# lin_reg_schematic_forpcb.net
KiCad netlist of a schematic drawn in EAGLE
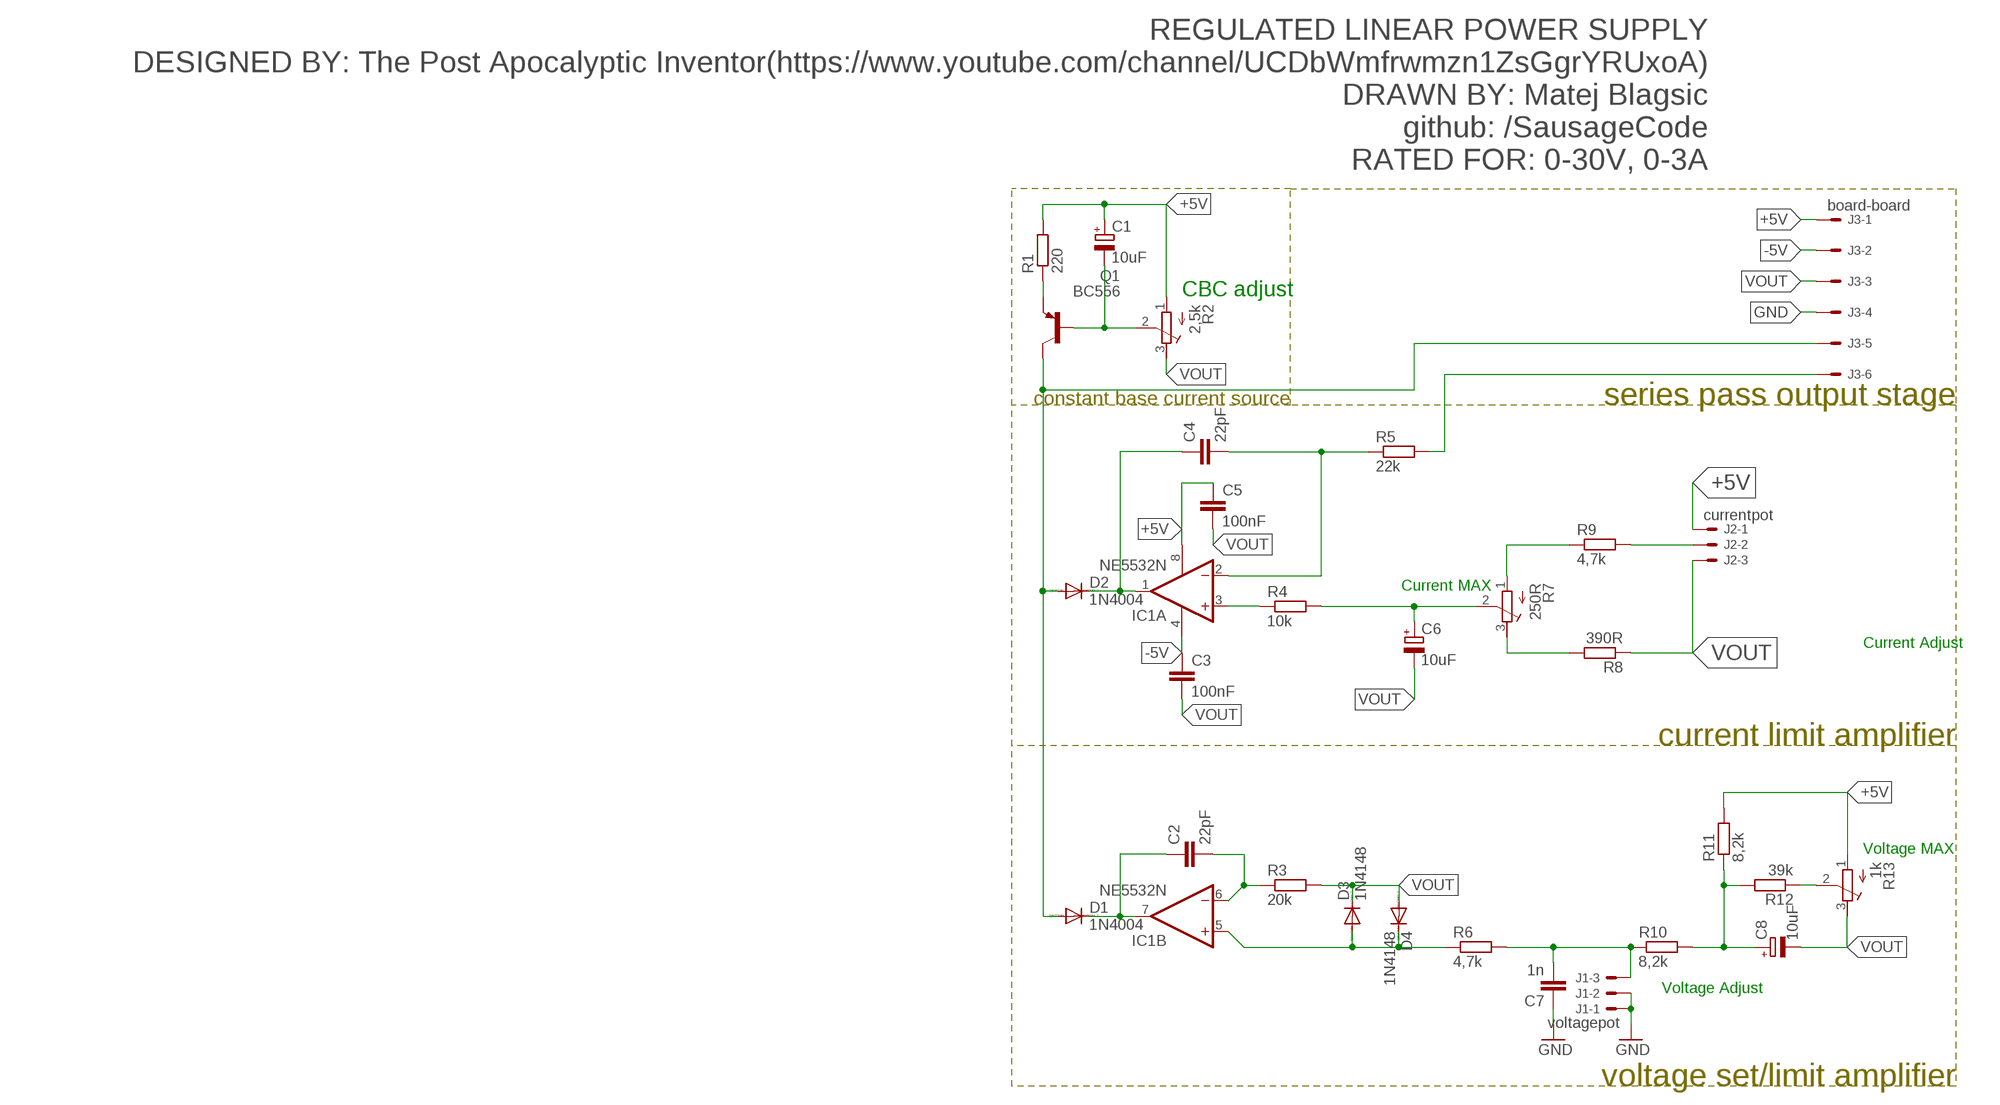
[diagram p0: schematic, sheet 1]

(export (version "E")
  (design (tool "Eeschema 10.0.6"))
  (components
    (comp (ref "C1")
      (value "10uF")
      (footprint "eagle-import:E2,5-5")
      (libsource (lib "eagle-import") (part "CPOL-EUE2.5-5"))
    )
    (comp (ref "C2")
      (value "22pF")
      (footprint "eagle-import:C025-025X050")
      (libsource (lib "eagle-import") (part "C-EU025-025X050"))
    )
    (comp (ref "C3")
      (value "100nF")
      (footprint "eagle-import:C025-025X050")
      (libsource (lib "eagle-import") (part "C-EU025-025X050"))
    )
    (comp (ref "C4")
      (value "22pF")
      (footprint "eagle-import:C025-025X050")
      (libsource (lib "eagle-import") (part "C-EU025-025X050"))
    )
    (comp (ref "C5")
      (value "100nF")
      (footprint "eagle-import:C025-025X050")
      (libsource (lib "eagle-import") (part "C-EU025-025X050"))
    )
    (comp (ref "C6")
      (value "10uF")
      (footprint "eagle-import:E2,5-5")
      (libsource (lib "eagle-import") (part "CPOL-EUE2.5-5"))
    )
    (comp (ref "C7")
      (value "1n")
      (footprint "eagle-import:C025-025X050")
      (libsource (lib "eagle-import") (part "C-EU025-025X050"))
    )
    (comp (ref "C8")
      (value "10uF")
      (footprint "eagle-import:E2,5-5")
      (libsource (lib "eagle-import") (part "CPOL-EUE2.5-5"))
    )
    (comp (ref "D1")
      (value "1N4004")
      (footprint "eagle-import:DO41-10")
      (libsource (lib "eagle-import") (part "1N4004"))
    )
    (comp (ref "D2")
      (value "1N4004")
      (footprint "eagle-import:DO41-10")
      (libsource (lib "eagle-import") (part "1N4004"))
    )
    (comp (ref "D3")
      (value "1N4148")
      (footprint "eagle-import:DO41-10")
      (libsource (lib "eagle-import") (part "1N4004"))
    )
    (comp (ref "D4")
      (value "1N4148")
      (footprint "eagle-import:DO41-10")
      (libsource (lib "eagle-import") (part "1N4004"))
    )
    (comp (ref "IC1")
      (value "NE5532N")
      (footprint "eagle-import:DIL08")
      (libsource (lib "eagle-import") (part "NE5532N"))
    )
    (comp (ref "J1")
      (value "voltagepot")
      (footprint "eagle-import:6410-03")
      (libsource (lib "eagle-import") (part "22-?-0327-2031"))
    )
    (comp (ref "J2")
      (value "currentpot")
      (footprint "eagle-import:6410-03")
      (libsource (lib "eagle-import") (part "22-?-0327-2031"))
    )
    (comp (ref "J3")
      (value "board-board")
      (footprint "eagle-import:6410-06")
      (libsource (lib "eagle-import") (part "22-?-0627-2061"))
    )
    (comp (ref "Q1")
      (value "BC556")
      (footprint "eagle-import:TO92-EBC")
      (libsource (lib "eagle-import") (part "BC556"))
    )
    (comp (ref "R1")
      (value "220")
      (footprint "eagle-import:0207_10")
      (libsource (lib "eagle-import") (part "R-EU_0207/10"))
    )
    (comp (ref "R2")
      (value "2,5k")
      (footprint "eagle-import:RTRIM64W")
      (libsource (lib "eagle-import") (part "R-TRIMM64W"))
    )
    (comp (ref "R3")
      (value "20k")
      (footprint "eagle-import:0207_10")
      (libsource (lib "eagle-import") (part "R-EU_0207/10"))
    )
    (comp (ref "R4")
      (value "10k")
      (footprint "eagle-import:0207_10")
      (libsource (lib "eagle-import") (part "R-EU_0207/10"))
    )
    (comp (ref "R5")
      (value "22k")
      (footprint "eagle-import:0207_10")
      (libsource (lib "eagle-import") (part "R-EU_0207/10"))
    )
    (comp (ref "R6")
      (value "4,7k")
      (footprint "eagle-import:0207_10")
      (libsource (lib "eagle-import") (part "R-EU_0207/10"))
    )
    (comp (ref "R7")
      (value "250R")
      (footprint "eagle-import:RTRIM64W")
      (libsource (lib "eagle-import") (part "R-TRIMM64W"))
    )
    (comp (ref "R8")
      (value "390R")
      (footprint "eagle-import:0207_10")
      (libsource (lib "eagle-import") (part "resistor_348_R-EU_0207/10"))
    )
    (comp (ref "R9")
      (value "4,7k")
      (footprint "eagle-import:0207_10")
      (libsource (lib "eagle-import") (part "resistor_348_R-EU_0207/10"))
    )
    (comp (ref "R10")
      (value "8,2k")
      (footprint "eagle-import:0207_10")
      (libsource (lib "eagle-import") (part "R-EU_0207/10"))
    )
    (comp (ref "R11")
      (value "8,2k")
      (footprint "eagle-import:0207_10")
      (libsource (lib "eagle-import") (part "R-EU_0207/10"))
    )
    (comp (ref "R12")
      (value "39k")
      (footprint "eagle-import:0207_10")
      (libsource (lib "eagle-import") (part "R-EU_0207/10"))
    )
    (comp (ref "R13")
      (value "1k")
      (footprint "eagle-import:RTRIM64W")
      (libsource (lib "eagle-import") (part "R-TRIMM64W"))
    )
  )
  (nets
    (net (code "1") (name "+5V") (class "Default")
      (node (ref "C1") (pin "+") (pinfunction "+_+") (pintype "passive"))
      (node (ref "C5") (pin "1") (pinfunction "1_1") (pintype "passive"))
      (node (ref "IC1") (pin "8") (pinfunction "V+_8") (pintype "power_in"))
      (node (ref "J2") (pin "1") (pinfunction "S_1") (pintype "passive"))
      (node (ref "J3") (pin "1") (pinfunction "S_1") (pintype "passive"))
      (node (ref "R1") (pin "2") (pinfunction "2_2") (pintype "passive"))
      (node (ref "R11") (pin "2") (pinfunction "2_2") (pintype "passive"))
      (node (ref "R13") (pin "1") (pinfunction "A_1") (pintype "passive"))
      (node (ref "R2") (pin "1") (pinfunction "A_1") (pintype "passive"))
    )
    (net (code "2") (name "-5V") (class "Default")
      (node (ref "C3") (pin "1") (pinfunction "1_1") (pintype "passive"))
      (node (ref "IC1") (pin "4") (pinfunction "V-_4") (pintype "power_in"))
      (node (ref "J3") (pin "2") (pinfunction "S_2") (pintype "passive"))
    )
    (net (code "3") (name "GND") (class "Default")
      (node (ref "C7") (pin "1") (pinfunction "1_1") (pintype "passive"))
      (node (ref "J1") (pin "1") (pinfunction "S_1") (pintype "passive"))
      (node (ref "J1") (pin "2") (pinfunction "S_2") (pintype "passive"))
      (node (ref "J3") (pin "4") (pinfunction "S_4") (pintype "passive"))
    )
    (net (code "4") (name "Net-(C8-Pad+)") (class "Default")
      (node (ref "C8") (pin "+") (pinfunction "+_+") (pintype "passive"))
      (node (ref "R10") (pin "2") (pinfunction "2_2") (pintype "passive"))
      (node (ref "R11") (pin "1") (pinfunction "1_1") (pintype "passive"))
      (node (ref "R12") (pin "2") (pinfunction "2_2") (pintype "passive"))
    )
    (net (code "5") (name "Net-(IC1A-+IN)") (class "Default")
      (node (ref "IC1") (pin "3") (pinfunction "+IN_3") (pintype "input"))
      (node (ref "R4") (pin "1") (pinfunction "1_1") (pintype "passive"))
    )
    (net (code "6") (name "Net-(IC1A--IN)") (class "Default")
      (node (ref "C4") (pin "2") (pinfunction "2_2") (pintype "passive"))
      (node (ref "IC1") (pin "2") (pinfunction "-IN_2") (pintype "input"))
      (node (ref "R5") (pin "1") (pinfunction "1_1") (pintype "passive"))
    )
    (net (code "7") (name "Net-(IC1A-OUT)") (class "Default")
      (node (ref "C4") (pin "1") (pinfunction "1_1") (pintype "passive"))
      (node (ref "D2") (pin "C") (pinfunction "C_C") (pintype "passive"))
      (node (ref "IC1") (pin "1") (pinfunction "OUT_1") (pintype "output"))
    )
    (net (code "8") (name "Net-(IC1B-+IN)") (class "Default")
      (node (ref "D3") (pin "A") (pinfunction "A_A") (pintype "passive"))
      (node (ref "D4") (pin "C") (pinfunction "C_C") (pintype "passive"))
      (node (ref "IC1") (pin "5") (pinfunction "+IN_5") (pintype "input"))
      (node (ref "R6") (pin "1") (pinfunction "1_1") (pintype "passive"))
    )
    (net (code "9") (name "Net-(IC1B--IN)") (class "Default")
      (node (ref "C2") (pin "2") (pinfunction "2_2") (pintype "passive"))
      (node (ref "IC1") (pin "6") (pinfunction "-IN_6") (pintype "input"))
      (node (ref "R3") (pin "1") (pinfunction "1_1") (pintype "passive"))
    )
    (net (code "10") (name "Net-(IC1B-OUT)") (class "Default")
      (node (ref "C2") (pin "1") (pinfunction "1_1") (pintype "passive"))
      (node (ref "D1") (pin "C") (pinfunction "C_C") (pintype "passive"))
      (node (ref "IC1") (pin "7") (pinfunction "OUT_7") (pintype "output"))
    )
    (net (code "11") (name "Net-(J1C-S)") (class "Default")
      (node (ref "C7") (pin "2") (pinfunction "2_2") (pintype "passive"))
      (node (ref "J1") (pin "3") (pinfunction "S_3") (pintype "passive"))
      (node (ref "R10") (pin "1") (pinfunction "1_1") (pintype "passive"))
      (node (ref "R6") (pin "2") (pinfunction "2_2") (pintype "passive"))
    )
    (net (code "12") (name "Net-(J2B-S)") (class "Default")
      (node (ref "J2") (pin "2") (pinfunction "S_2") (pintype "passive"))
      (node (ref "R9") (pin "2") (pinfunction "2_2") (pintype "passive"))
    )
    (net (code "13") (name "Net-(J3E-S)") (class "Default")
      (node (ref "D1") (pin "A") (pinfunction "A_A") (pintype "passive"))
      (node (ref "D2") (pin "A") (pinfunction "A_A") (pintype "passive"))
      (node (ref "J3") (pin "5") (pinfunction "S_5") (pintype "passive"))
      (node (ref "Q1") (pin "C") (pinfunction "C_C") (pintype "passive"))
    )
    (net (code "14") (name "Net-(J3F-S)") (class "Default")
      (node (ref "J3") (pin "6") (pinfunction "S_6") (pintype "passive"))
      (node (ref "R5") (pin "2") (pinfunction "2_2") (pintype "passive"))
    )
    (net (code "15") (name "Net-(Q1-PadE)") (class "Default")
      (node (ref "Q1") (pin "E") (pinfunction "E_E") (pintype "passive"))
      (node (ref "R1") (pin "1") (pinfunction "1_1") (pintype "passive"))
    )
    (net (code "16") (name "Net-(R2-S)") (class "Default")
      (node (ref "C1") (pin "-") (pinfunction "-_-") (pintype "passive"))
      (node (ref "Q1") (pin "B") (pinfunction "B_B") (pintype "passive"))
      (node (ref "R2") (pin "2") (pinfunction "S_2") (pintype "passive"))
    )
    (net (code "17") (name "Net-(R7-A)") (class "Default")
      (node (ref "R7") (pin "1") (pinfunction "A_1") (pintype "passive"))
      (node (ref "R9") (pin "1") (pinfunction "1_1") (pintype "passive"))
    )
    (net (code "18") (name "Net-(R7-E)") (class "Default")
      (node (ref "R7") (pin "3") (pinfunction "E_3") (pintype "passive"))
      (node (ref "R8") (pin "2") (pinfunction "2_2") (pintype "passive"))
    )
    (net (code "19") (name "Net-(R7-S)") (class "Default")
      (node (ref "C6") (pin "+") (pinfunction "+_+") (pintype "passive"))
      (node (ref "R4") (pin "2") (pinfunction "2_2") (pintype "passive"))
      (node (ref "R7") (pin "2") (pinfunction "S_2") (pintype "passive"))
    )
    (net (code "20") (name "Net-(R13-S)") (class "Default")
      (node (ref "R12") (pin "1") (pinfunction "1_1") (pintype "passive"))
      (node (ref "R13") (pin "2") (pinfunction "S_2") (pintype "passive"))
    )
    (net (code "21") (name "VOUT") (class "Default")
      (node (ref "C3") (pin "2") (pinfunction "2_2") (pintype "passive"))
      (node (ref "C5") (pin "2") (pinfunction "2_2") (pintype "passive"))
      (node (ref "C6") (pin "-") (pinfunction "-_-") (pintype "passive"))
      (node (ref "C8") (pin "-") (pinfunction "-_-") (pintype "passive"))
      (node (ref "D3") (pin "C") (pinfunction "C_C") (pintype "passive"))
      (node (ref "D4") (pin "A") (pinfunction "A_A") (pintype "passive"))
      (node (ref "J2") (pin "3") (pinfunction "S_3") (pintype "passive"))
      (node (ref "J3") (pin "3") (pinfunction "S_3") (pintype "passive"))
      (node (ref "R13") (pin "3") (pinfunction "E_3") (pintype "passive"))
      (node (ref "R2") (pin "3") (pinfunction "E_3") (pintype "passive"))
      (node (ref "R3") (pin "2") (pinfunction "2_2") (pintype "passive"))
      (node (ref "R8") (pin "1") (pinfunction "1_1") (pintype "passive"))
    )
  )
)
